# RF-Gen_Controller.net
KiCad netlist of a schematic drawn in EAGLE
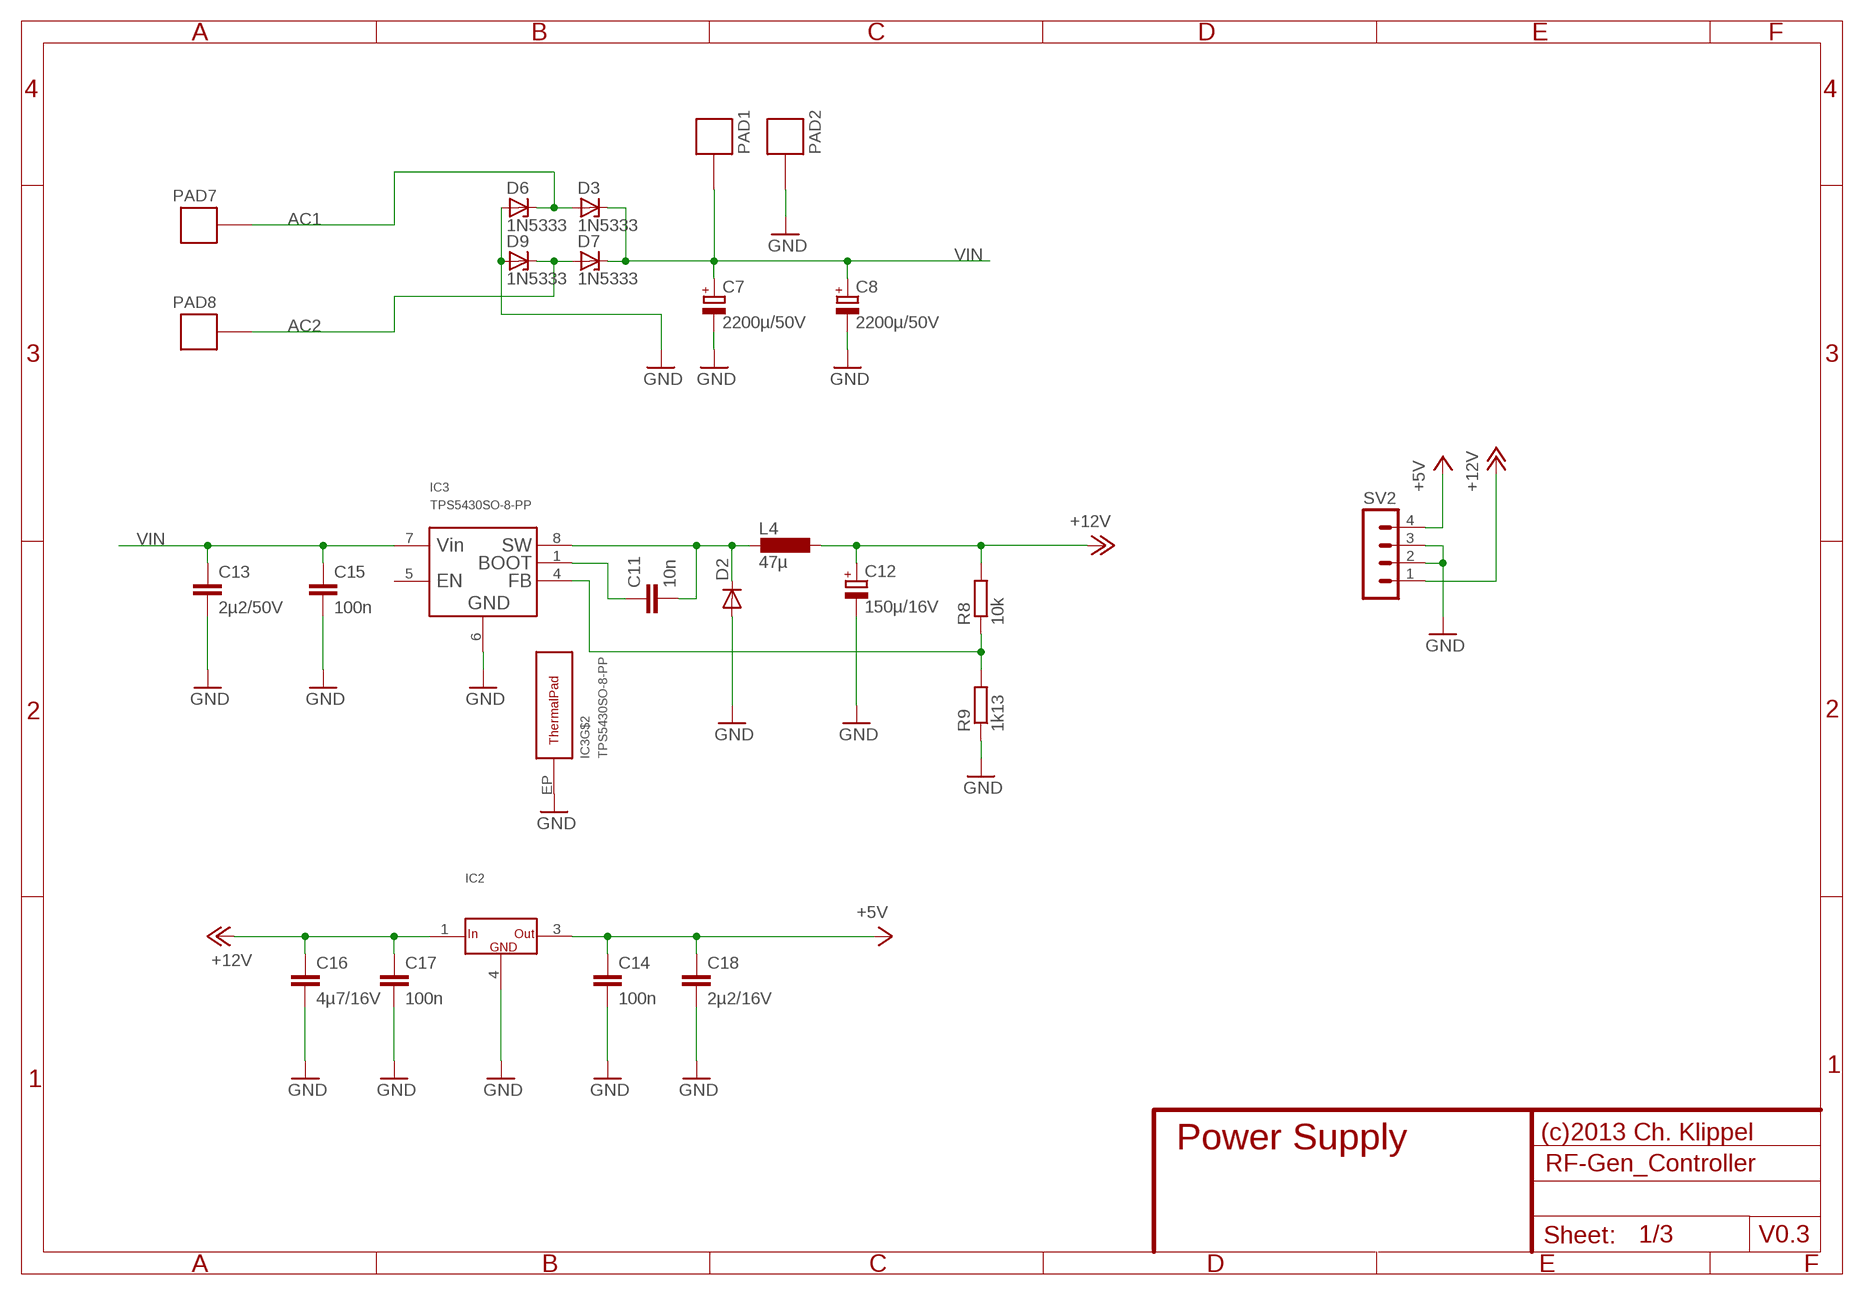
[diagram p0: schematic, sheet 1]
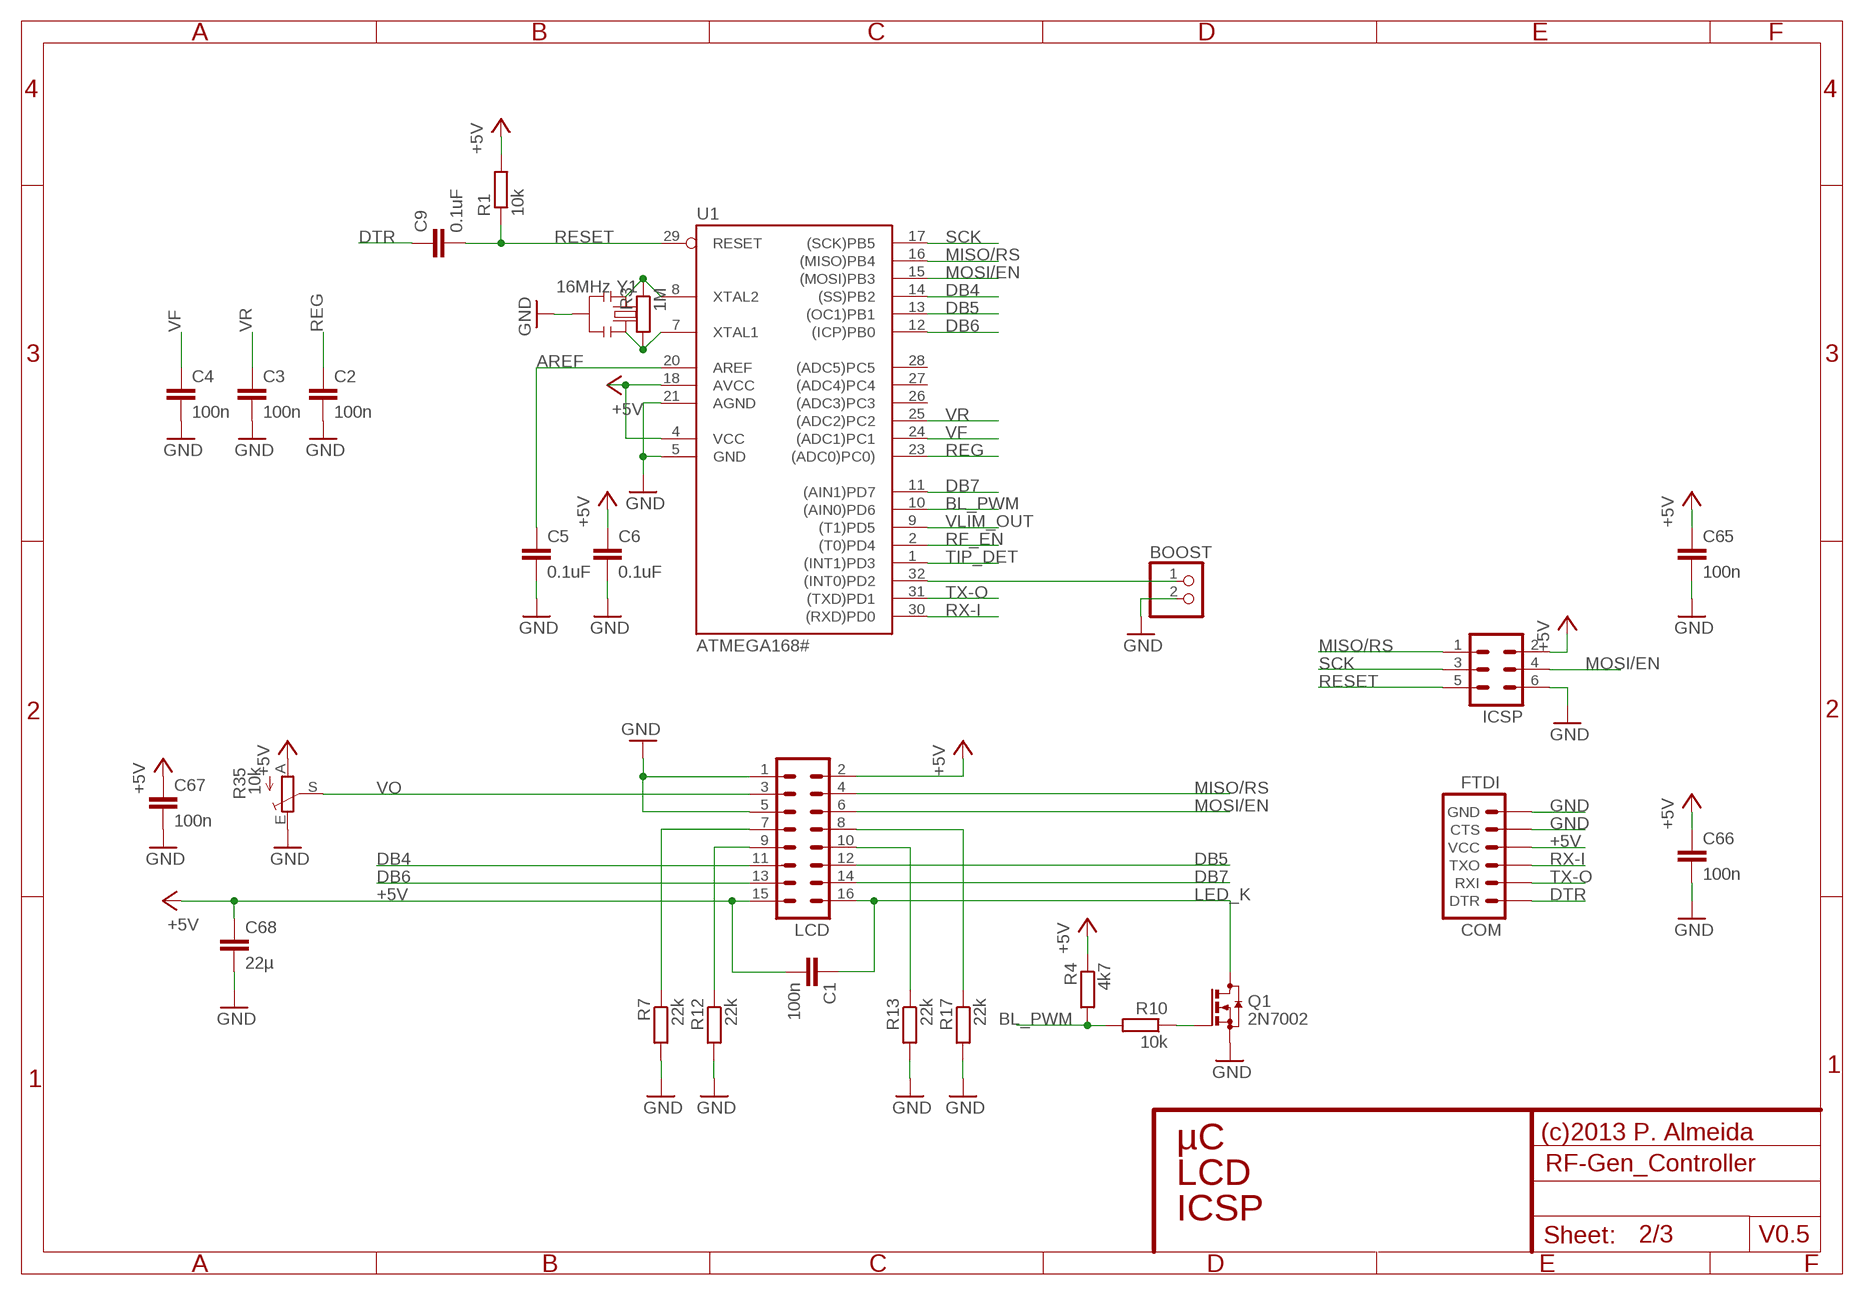
[diagram p1: schematic, sheet 2]
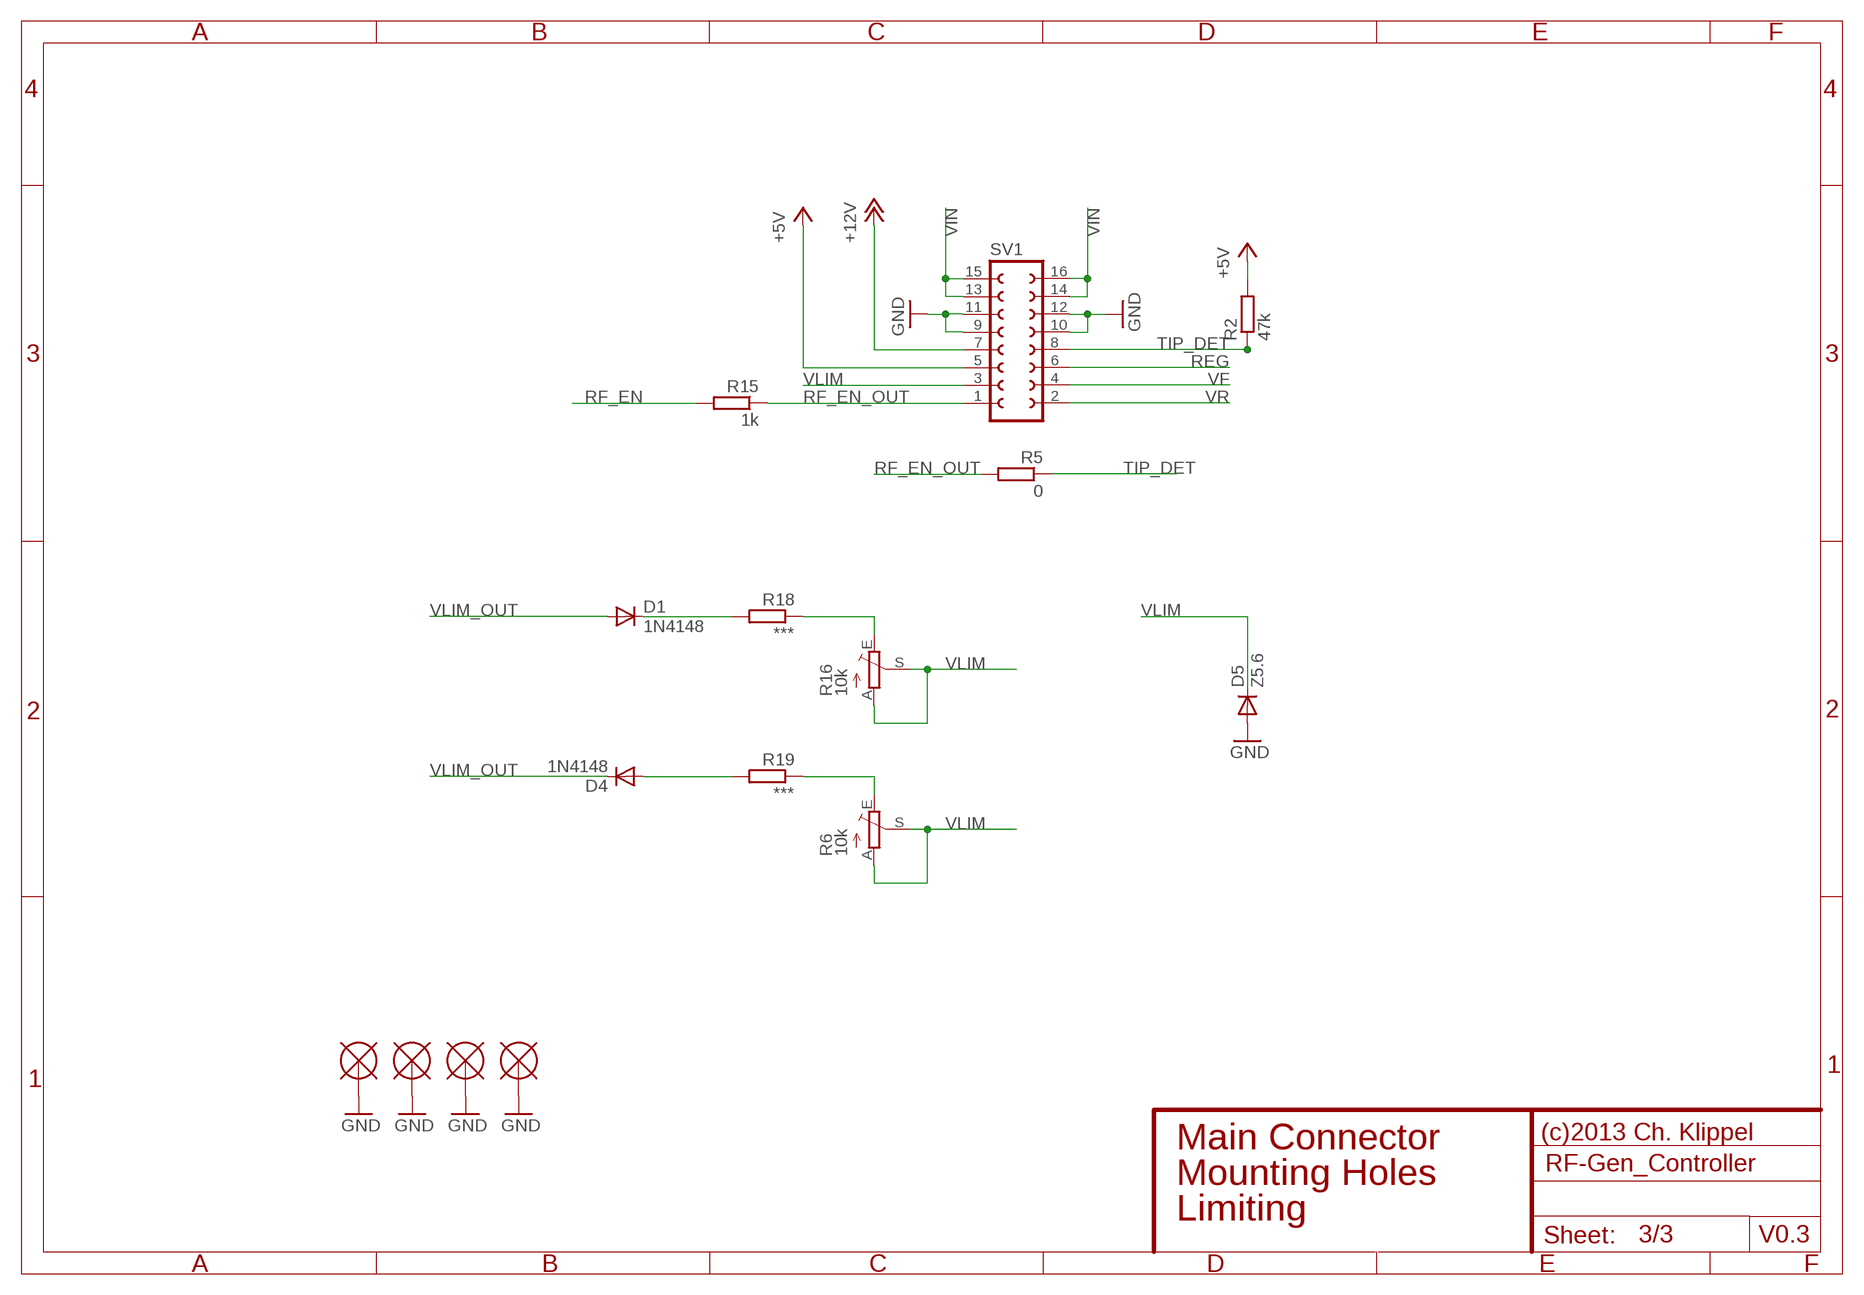
[diagram p2: schematic, sheet 3]

(export (version "E")
  (design (tool "Eeschema 10.0.6"))
  (components
    (comp (ref "D1")
      (value "1N4148")
      (footprint "eagle-import:LL-34")
      (libsource (lib "eagle-import") (part "DIODE-LL-34"))
    )
    (comp (ref "D4")
      (value "1N4148")
      (footprint "eagle-import:LL-34")
      (libsource (lib "eagle-import") (part "DIODE-LL-34"))
    )
    (comp (ref "D5")
      (value "Z5.6")
      (footprint "eagle-import:LL-34")
      (libsource (lib "eagle-import") (part "DIODE-LL-34"))
    )
    (comp (ref "R2")
      (value "47k")
      (footprint "eagle-import:R_0805_REFLOW")
      (libsource (lib "eagle-import") (part "R-EU-0805"))
    )
    (comp (ref "R5")
      (value "0")
      (footprint "eagle-import:R_0805_REFLOW")
      (libsource (lib "eagle-import") (part "R-EU-0805"))
    )
    (comp (ref "R6")
      (value "10k")
      (footprint "eagle-import:3364W")
      (libsource (lib "eagle-import") (part "TRIM_EU-3364W"))
    )
    (comp (ref "R15")
      (value "1k")
      (footprint "eagle-import:R_0805_REFLOW")
      (libsource (lib "eagle-import") (part "R-EU-0805"))
    )
    (comp (ref "R16")
      (value "10k")
      (footprint "eagle-import:3364W")
      (libsource (lib "eagle-import") (part "TRIM_EU-3364W"))
    )
    (comp (ref "R18")
      (value "***")
      (footprint "eagle-import:R_0805_REFLOW")
      (libsource (lib "eagle-import") (part "R-EU-0805"))
    )
    (comp (ref "R19")
      (value "***")
      (footprint "eagle-import:R_0805_REFLOW")
      (libsource (lib "eagle-import") (part "R-EU-0805"))
    )
    (comp (ref "SV1")
      (value "FE08-2")
      (footprint "eagle-import:FE08-2")
      (libsource (lib "eagle-import") (part "FE08-2"))
    )
    (comp (ref "U$6")
      (value "MOUNTPADM3_WASHER")
      (footprint "eagle-import:PAD_M3_WASHER")
      (libsource (lib "eagle-import") (part "MOUNTPADM3_WASHER"))
    )
    (comp (ref "U$7")
      (value "MOUNTPADM3_WASHER")
      (footprint "eagle-import:PAD_M3_WASHER")
      (libsource (lib "eagle-import") (part "MOUNTPADM3_WASHER"))
    )
    (comp (ref "U$8")
      (value "MOUNTPADM3_WASHER")
      (footprint "eagle-import:PAD_M3_WASHER")
      (libsource (lib "eagle-import") (part "MOUNTPADM3_WASHER"))
    )
    (comp (ref "U$9")
      (value "MOUNTPADM3_WASHER")
      (footprint "eagle-import:PAD_M3_WASHER")
      (libsource (lib "eagle-import") (part "MOUNTPADM3_WASHER"))
    )
    (comp (ref "C7")
      (value "2200µ/50V")
      (footprint "eagle-import:CAP_EEUHD1H_VERT2")
      (libsource (lib "eagle-import") (part "C-POL-EU-EEUHD1H_VERT2"))
    )
    (comp (ref "C8")
      (value "2200µ/50V")
      (footprint "eagle-import:CAP_EEUHD1H_VERT2")
      (libsource (lib "eagle-import") (part "C-POL-EU-EEUHD1H_VERT2"))
    )
    (comp (ref "C11")
      (value "10n")
      (footprint "eagle-import:C_1206_REFLOW")
      (libsource (lib "eagle-import") (part "C-EU-1206"))
    )
    (comp (ref "C12")
      (value "150µ/16V")
      (footprint "eagle-import:CAP_AL_100_108")
      (libsource (lib "eagle-import") (part "C-POL-EU-AL_100_108"))
    )
    (comp (ref "C13")
      (value "2µ2/50V")
      (footprint "eagle-import:C_1210_REFLOW")
      (libsource (lib "eagle-import") (part "C-EU-1210"))
    )
    (comp (ref "C14")
      (value "100n")
      (footprint "eagle-import:C_0805_REFLOW")
      (libsource (lib "eagle-import") (part "C-EU-0805"))
    )
    (comp (ref "C15")
      (value "100n")
      (footprint "eagle-import:C_0805_REFLOW")
      (libsource (lib "eagle-import") (part "C-EU-0805"))
    )
    (comp (ref "C16")
      (value "4µ7/16V")
      (footprint "eagle-import:C_1210_REFLOW")
      (libsource (lib "eagle-import") (part "C-EU-1210"))
    )
    (comp (ref "C17")
      (value "100n")
      (footprint "eagle-import:C_0805_REFLOW")
      (libsource (lib "eagle-import") (part "C-EU-0805"))
    )
    (comp (ref "C18")
      (value "2µ2/16V")
      (footprint "eagle-import:C_1210_REFLOW")
      (libsource (lib "eagle-import") (part "C-EU-1210"))
    )
    (comp (ref "D2")
      (value "DIODE-SMB")
      (footprint "eagle-import:SMB")
      (libsource (lib "eagle-import") (part "DIODE-SMB"))
    )
    (comp (ref "D3")
      (value "1N5333")
      (footprint "eagle-import:C1702-15")
      (libsource (lib "eagle-import") (part "1N5333"))
    )
    (comp (ref "D6")
      (value "1N5333")
      (footprint "eagle-import:C1702-15")
      (libsource (lib "eagle-import") (part "1N5333"))
    )
    (comp (ref "D7")
      (value "1N5333")
      (footprint "eagle-import:C1702-15")
      (libsource (lib "eagle-import") (part "1N5333"))
    )
    (comp (ref "D9")
      (value "1N5333")
      (footprint "eagle-import:C1702-15")
      (libsource (lib "eagle-import") (part "1N5333"))
    )
    (comp (ref "IC2")
      (value "VREG_3DPAK-3")
      (footprint "eagle-import:DPAK-3")
      (libsource (lib "eagle-import") (part "VREG_3DPAK-3"))
    )
    (comp (ref "IC3")
      (value "TPS5430SO-8-PP")
      (footprint "eagle-import:SO-8-PP")
      (libsource (lib "eagle-import") (part "TPS5430SO-8-PP"))
    )
    (comp (ref "L4")
      (value "47µ")
      (footprint "eagle-import:SSR1260")
      (libsource (lib "eagle-import") (part "L-EU-SSR1260"))
    )
    (comp (ref "PAD1")
      (value "SOLPAD5MM")
      (footprint "eagle-import:SOLPAD_5")
      (libsource (lib "eagle-import") (part "SOLPAD5MM"))
    )
    (comp (ref "PAD2")
      (value "SOLPAD5MM")
      (footprint "eagle-import:SOLPAD_5")
      (libsource (lib "eagle-import") (part "SOLPAD5MM"))
    )
    (comp (ref "PAD7")
      (value "SOLPAD5MM")
      (footprint "eagle-import:SOLPAD_5")
      (libsource (lib "eagle-import") (part "SOLPAD5MM"))
    )
    (comp (ref "PAD8")
      (value "SOLPAD5MM")
      (footprint "eagle-import:SOLPAD_5")
      (libsource (lib "eagle-import") (part "SOLPAD5MM"))
    )
    (comp (ref "R8")
      (value "10k")
      (footprint "eagle-import:R_0805_REFLOW")
      (libsource (lib "eagle-import") (part "R-EU-0805"))
    )
    (comp (ref "R9")
      (value "1k13")
      (footprint "eagle-import:R_0805_REFLOW")
      (libsource (lib "eagle-import") (part "R-EU-0805"))
    )
    (comp (ref "SV2")
      (value "MA04-1")
      (footprint "eagle-import:MA04-1")
      (libsource (lib "eagle-import") (part "MA04-1"))
    )
    (comp (ref "BOOST")
      (value "PINHD-1X2/90")
      (footprint "eagle-import:1X02_90")
      (libsource (lib "eagle-import") (part "PINHD-1X2/90"))
    )
    (comp (ref "C1")
      (value "100n")
      (footprint "eagle-import:C_0805_REFLOW")
      (libsource (lib "eagle-import") (part "C-EU-0805"))
    )
    (comp (ref "C2")
      (value "100n")
      (footprint "eagle-import:C_0805_REFLOW")
      (libsource (lib "eagle-import") (part "C-EU-0805"))
    )
    (comp (ref "C3")
      (value "100n")
      (footprint "eagle-import:C_0805_REFLOW")
      (libsource (lib "eagle-import") (part "C-EU-0805"))
    )
    (comp (ref "C4")
      (value "100n")
      (footprint "eagle-import:C_0805_REFLOW")
      (libsource (lib "eagle-import") (part "C-EU-0805"))
    )
    (comp (ref "C5")
      (value "0.1uF")
      (footprint "eagle-import:C_0805_REFLOW")
      (libsource (lib "eagle-import") (part "C-EU-0805"))
    )
    (comp (ref "C6")
      (value "0.1uF")
      (footprint "eagle-import:C_0805_REFLOW")
      (libsource (lib "eagle-import") (part "C-EU-0805"))
    )
    (comp (ref "C9")
      (value "0.1uF")
      (footprint "eagle-import:C_0805_REFLOW")
      (libsource (lib "eagle-import") (part "C-EU-0805"))
    )
    (comp (ref "C65")
      (value "100n")
      (footprint "eagle-import:C_0805_REFLOW")
      (libsource (lib "eagle-import") (part "C-EU-0805"))
    )
    (comp (ref "C66")
      (value "100n")
      (footprint "eagle-import:C_0805_REFLOW")
      (libsource (lib "eagle-import") (part "C-EU-0805"))
    )
    (comp (ref "C67")
      (value "100n")
      (footprint "eagle-import:C_0805_REFLOW")
      (libsource (lib "eagle-import") (part "C-EU-0805"))
    )
    (comp (ref "C68")
      (value "22µ")
      (footprint "eagle-import:C_1206_REFLOW")
      (libsource (lib "eagle-import") (part "C-EU-1206"))
    )
    (comp (ref "FTDI")
      (value "COM")
      (footprint "eagle-import:1X06")
      (libsource (lib "eagle-import") (part "ARDUINO_SERIAL_PROGRAMPTH"))
    )
    (comp (ref "ICSP")
      (value "ML6")
      (footprint "eagle-import:ML6")
      (libsource (lib "eagle-import") (part "ML6"))
    )
    (comp (ref "LCD")
      (value "ML16")
      (footprint "eagle-import:ML16")
      (libsource (lib "eagle-import") (part "ML16"))
    )
    (comp (ref "Q1")
      (value "2N7002")
      (footprint "eagle-import:SOT23")
      (libsource (lib "eagle-import") (part "BSS123"))
    )
    (comp (ref "R1")
      (value "10k")
      (footprint "eagle-import:R_0805_REFLOW")
      (libsource (lib "eagle-import") (part "R-EU-0805"))
    )
    (comp (ref "R3")
      (value "1M")
      (footprint "eagle-import:R_0805_REFLOW")
      (libsource (lib "eagle-import") (part "R-EU-0805"))
    )
    (comp (ref "R4")
      (value "4k7")
      (footprint "eagle-import:R_0805_REFLOW")
      (libsource (lib "eagle-import") (part "R-EU-0805"))
    )
    (comp (ref "R7")
      (value "22k")
      (footprint "eagle-import:R_0805_REFLOW")
      (libsource (lib "eagle-import") (part "R-EU-0805"))
    )
    (comp (ref "R10")
      (value "10k")
      (footprint "eagle-import:R_0805_REFLOW")
      (libsource (lib "eagle-import") (part "R-EU-0805"))
    )
    (comp (ref "R12")
      (value "22k")
      (footprint "eagle-import:R_0805_REFLOW")
      (libsource (lib "eagle-import") (part "R-EU-0805"))
    )
    (comp (ref "R13")
      (value "22k")
      (footprint "eagle-import:R_0805_REFLOW")
      (libsource (lib "eagle-import") (part "R-EU-0805"))
    )
    (comp (ref "R17")
      (value "22k")
      (footprint "eagle-import:R_0805_REFLOW")
      (libsource (lib "eagle-import") (part "R-EU-0805"))
    )
    (comp (ref "R35")
      (value "10k")
      (footprint "eagle-import:3364W")
      (libsource (lib "eagle-import") (part "TRIM_EU-3364W"))
    )
    (comp (ref "U1")
      (value "ATMEGA168#")
      (footprint "eagle-import:TQFP32-08")
      (libsource (lib "eagle-import") (part "AT90S4433A"))
    )
    (comp (ref "Y1")
      (value "16MHz")
      (footprint "eagle-import:RESONATOR-SMD")
      (libsource (lib "eagle-import") (part "RESONATORSMD"))
    )
  )
  (nets
    (net (code "1") (name "+5V") (class "Default")
      (node (ref "C1") (pin "P$2") (pinfunction "2_P$2") (pintype "passive"))
      (node (ref "C14") (pin "P$1") (pinfunction "1_P$1") (pintype "passive"))
      (node (ref "C18") (pin "P$1") (pinfunction "1_P$1") (pintype "passive"))
      (node (ref "C6") (pin "P$1") (pinfunction "1_P$1") (pintype "passive"))
      (node (ref "C65") (pin "P$1") (pinfunction "1_P$1") (pintype "passive"))
      (node (ref "C66") (pin "P$1") (pinfunction "1_P$1") (pintype "passive"))
      (node (ref "C67") (pin "P$1") (pinfunction "1_P$1") (pintype "passive"))
      (node (ref "C68") (pin "P$1") (pinfunction "1_P$1") (pintype "passive"))
      (node (ref "FTDI") (pin "4") (pinfunction "VCC_4") (pintype "passive"))
      (node (ref "IC2") (pin "3") (pinfunction "OUT_3") (pintype "bidirectional"))
      (node (ref "ICSP") (pin "2") (pinfunction "2_2") (pintype "passive"))
      (node (ref "LCD") (pin "15") (pinfunction "15_15") (pintype "passive"))
      (node (ref "LCD") (pin "2") (pinfunction "2_2") (pintype "passive"))
      (node (ref "R1") (pin "P$2") (pinfunction "2_P$2") (pintype "passive"))
      (node (ref "R2") (pin "P$2") (pinfunction "2_P$2") (pintype "passive"))
      (node (ref "R35") (pin "A") (pinfunction "A_A") (pintype "passive"))
      (node (ref "R4") (pin "P$1") (pinfunction "1_P$1") (pintype "passive"))
      (node (ref "SV1") (pin "5") (pinfunction "5_5") (pintype "passive"))
      (node (ref "SV2") (pin "4") (pinfunction "4_4") (pintype "passive"))
      (node (ref "U1") (pin "18") (pinfunction "AVCC_18") (pintype "power_in"))
      (node (ref "U1") (pin "4") (pinfunction "VCC_4") (pintype "power_in"))
    )
    (net (code "2") (name "+12V") (class "Default")
      (node (ref "C12") (pin "+") (pinfunction "+_+") (pintype "passive"))
      (node (ref "C16") (pin "P$1") (pinfunction "1_P$1") (pintype "passive"))
      (node (ref "C17") (pin "P$1") (pinfunction "1_P$1") (pintype "passive"))
      (node (ref "IC2") (pin "1") (pinfunction "IN_1") (pintype "bidirectional"))
      (node (ref "L4") (pin "1") (pinfunction "1_1") (pintype "passive"))
      (node (ref "R8") (pin "P$2") (pinfunction "2_P$2") (pintype "passive"))
      (node (ref "SV1") (pin "7") (pinfunction "7_7") (pintype "passive"))
      (node (ref "SV2") (pin "1") (pinfunction "1_1") (pintype "passive"))
    )
    (net (code "3") (name "AC1") (class "Default")
      (node (ref "D3") (pin "A") (pinfunction "A_A") (pintype "passive"))
      (node (ref "D6") (pin "C") (pinfunction "C_C") (pintype "passive"))
      (node (ref "PAD7") (pin "P$1") (pinfunction "P$1_P$1") (pintype "bidirectional"))
    )
    (net (code "4") (name "AC2") (class "Default")
      (node (ref "D7") (pin "A") (pinfunction "A_A") (pintype "passive"))
      (node (ref "D9") (pin "C") (pinfunction "C_C") (pintype "passive"))
      (node (ref "PAD8") (pin "P$1") (pinfunction "P$1_P$1") (pintype "bidirectional"))
    )
    (net (code "5") (name "AREF") (class "Default")
      (node (ref "C5") (pin "P$1") (pinfunction "1_P$1") (pintype "passive"))
      (node (ref "U1") (pin "20") (pinfunction "AREF_20") (pintype "power_in"))
    )
    (net (code "6") (name "BL_PWM") (class "Default")
      (node (ref "R10") (pin "P$2") (pinfunction "2_P$2") (pintype "passive"))
      (node (ref "R4") (pin "P$2") (pinfunction "2_P$2") (pintype "passive"))
      (node (ref "U1") (pin "10") (pinfunction "(AIN0)PD6_10") (pintype "bidirectional"))
    )
    (net (code "7") (name "DB4") (class "Default")
      (node (ref "LCD") (pin "11") (pinfunction "11_11") (pintype "passive"))
      (node (ref "U1") (pin "14") (pinfunction "(SS)PB2_14") (pintype "bidirectional"))
    )
    (net (code "8") (name "DB5") (class "Default")
      (node (ref "LCD") (pin "12") (pinfunction "12_12") (pintype "passive"))
      (node (ref "U1") (pin "13") (pinfunction "(OC1)PB1_13") (pintype "bidirectional"))
    )
    (net (code "9") (name "DB6") (class "Default")
      (node (ref "LCD") (pin "13") (pinfunction "13_13") (pintype "passive"))
      (node (ref "U1") (pin "12") (pinfunction "(ICP)PB0_12") (pintype "bidirectional"))
    )
    (net (code "10") (name "DB7") (class "Default")
      (node (ref "LCD") (pin "14") (pinfunction "14_14") (pintype "passive"))
      (node (ref "U1") (pin "11") (pinfunction "(AIN1)PD7_11") (pintype "bidirectional"))
    )
    (net (code "11") (name "DTR") (class "Default")
      (node (ref "C9") (pin "P$1") (pinfunction "1_P$1") (pintype "passive"))
      (node (ref "FTDI") (pin "1") (pinfunction "DTR_1") (pintype "passive"))
    )
    (net (code "12") (name "GND") (class "Default")
      (node (ref "BOOST") (pin "2") (pinfunction "2_2") (pintype "passive"))
      (node (ref "C12") (pin "-") (pinfunction "-_-") (pintype "passive"))
      (node (ref "C13") (pin "P$2") (pinfunction "2_P$2") (pintype "passive"))
      (node (ref "C14") (pin "P$2") (pinfunction "2_P$2") (pintype "passive"))
      (node (ref "C15") (pin "P$2") (pinfunction "2_P$2") (pintype "passive"))
      (node (ref "C16") (pin "P$2") (pinfunction "2_P$2") (pintype "passive"))
      (node (ref "C17") (pin "P$2") (pinfunction "2_P$2") (pintype "passive"))
      (node (ref "C18") (pin "P$2") (pinfunction "2_P$2") (pintype "passive"))
      (node (ref "C2") (pin "P$2") (pinfunction "2_P$2") (pintype "passive"))
      (node (ref "C3") (pin "P$2") (pinfunction "2_P$2") (pintype "passive"))
      (node (ref "C4") (pin "P$2") (pinfunction "2_P$2") (pintype "passive"))
      (node (ref "C5") (pin "P$2") (pinfunction "2_P$2") (pintype "passive"))
      (node (ref "C6") (pin "P$2") (pinfunction "2_P$2") (pintype "passive"))
      (node (ref "C65") (pin "P$2") (pinfunction "2_P$2") (pintype "passive"))
      (node (ref "C66") (pin "P$2") (pinfunction "2_P$2") (pintype "passive"))
      (node (ref "C67") (pin "P$2") (pinfunction "2_P$2") (pintype "passive"))
      (node (ref "C68") (pin "P$2") (pinfunction "2_P$2") (pintype "passive"))
      (node (ref "C7") (pin "-") (pinfunction "-_-") (pintype "passive"))
      (node (ref "C8") (pin "-") (pinfunction "-_-") (pintype "passive"))
      (node (ref "D2") (pin "A") (pinfunction "A_A") (pintype "passive"))
      (node (ref "D5") (pin "A") (pinfunction "A_A") (pintype "passive"))
      (node (ref "D6") (pin "A") (pinfunction "A_A") (pintype "passive"))
      (node (ref "D9") (pin "A") (pinfunction "A_A") (pintype "passive"))
      (node (ref "FTDI") (pin "5") (pinfunction "CTS_5") (pintype "passive"))
      (node (ref "FTDI") (pin "6") (pinfunction "GND_6") (pintype "passive"))
      (node (ref "IC2") (pin "4") (pinfunction "GND_4") (pintype "bidirectional"))
      (node (ref "IC3") (pin "6") (pinfunction "GND_6") (pintype "bidirectional"))
      (node (ref "IC3") (pin "EP") (pinfunction "THERMALPAD_EP") (pintype "bidirectional"))
      (node (ref "ICSP") (pin "6") (pinfunction "6_6") (pintype "passive"))
      (node (ref "LCD") (pin "1") (pinfunction "1_1") (pintype "passive"))
      (node (ref "LCD") (pin "5") (pinfunction "5_5") (pintype "passive"))
      (node (ref "PAD2") (pin "P$1") (pinfunction "P$1_P$1") (pintype "bidirectional"))
      (node (ref "Q1") (pin "2") (pinfunction "S_2") (pintype "passive"))
      (node (ref "R12") (pin "P$2") (pinfunction "2_P$2") (pintype "passive"))
      (node (ref "R13") (pin "P$2") (pinfunction "2_P$2") (pintype "passive"))
      (node (ref "R17") (pin "P$2") (pinfunction "2_P$2") (pintype "passive"))
      (node (ref "R35") (pin "E") (pinfunction "E_E") (pintype "passive"))
      (node (ref "R7") (pin "P$2") (pinfunction "2_P$2") (pintype "passive"))
      (node (ref "R9") (pin "P$1") (pinfunction "1_P$1") (pintype "passive"))
      (node (ref "SV1") (pin "10") (pinfunction "10_10") (pintype "passive"))
      (node (ref "SV1") (pin "11") (pinfunction "11_11") (pintype "passive"))
      (node (ref "SV1") (pin "12") (pinfunction "12_12") (pintype "passive"))
      (node (ref "SV1") (pin "9") (pinfunction "9_9") (pintype "passive"))
      (node (ref "SV2") (pin "2") (pinfunction "2_2") (pintype "passive"))
      (node (ref "SV2") (pin "3") (pinfunction "3_3") (pintype "passive"))
      (node (ref "U$6") (pin "P$1") (pinfunction "P$1_P$1") (pintype "bidirectional"))
      (node (ref "U$7") (pin "P$1") (pinfunction "P$1_P$1") (pintype "bidirectional"))
      (node (ref "U$8") (pin "P$1") (pinfunction "P$1_P$1") (pintype "bidirectional"))
      (node (ref "U$9") (pin "P$1") (pinfunction "P$1_P$1") (pintype "bidirectional"))
      (node (ref "U1") (pin "21") (pinfunction "AGND_21") (pintype "power_in"))
      (node (ref "U1") (pin "5") (pinfunction "GND_5") (pintype "power_in"))
      (node (ref "Y1") (pin "2") (pinfunction "2_2") (pintype "passive"))
    )
    (net (code "13") (name "LED_K") (class "Default")
      (node (ref "C1") (pin "P$1") (pinfunction "1_P$1") (pintype "passive"))
      (node (ref "LCD") (pin "16") (pinfunction "16_16") (pintype "passive"))
      (node (ref "Q1") (pin "3") (pinfunction "D_3") (pintype "passive"))
    )
    (net (code "14") (name "MISO{slash}RS") (class "Default")
      (node (ref "ICSP") (pin "1") (pinfunction "1_1") (pintype "passive"))
      (node (ref "LCD") (pin "4") (pinfunction "4_4") (pintype "passive"))
      (node (ref "U1") (pin "16") (pinfunction "(MISO)PB4_16") (pintype "bidirectional"))
    )
    (net (code "15") (name "MOSI{slash}EN") (class "Default")
      (node (ref "ICSP") (pin "4") (pinfunction "4_4") (pintype "passive"))
      (node (ref "LCD") (pin "6") (pinfunction "6_6") (pintype "passive"))
      (node (ref "U1") (pin "15") (pinfunction "(MOSI)PB3_15") (pintype "bidirectional"))
    )
    (net (code "16") (name "Net-(C11-1)") (class "Default")
      (node (ref "C11") (pin "P$1") (pinfunction "1_P$1") (pintype "passive"))
      (node (ref "IC3") (pin "1") (pinfunction "BOOT_1") (pintype "bidirectional"))
    )
    (net (code "17") (name "Net-(C11-2)") (class "Default")
      (node (ref "C11") (pin "P$2") (pinfunction "2_P$2") (pintype "passive"))
      (node (ref "D2") (pin "C") (pinfunction "C_C") (pintype "passive"))
      (node (ref "IC3") (pin "8") (pinfunction "SW_8") (pintype "bidirectional"))
      (node (ref "L4") (pin "2") (pinfunction "2_2") (pintype "passive"))
    )
    (net (code "18") (name "Net-(IC3A-FB)") (class "Default")
      (node (ref "IC3") (pin "4") (pinfunction "FB_4") (pintype "bidirectional"))
      (node (ref "R8") (pin "P$1") (pinfunction "1_P$1") (pintype "passive"))
      (node (ref "R9") (pin "P$2") (pinfunction "2_P$2") (pintype "passive"))
    )
    (net (code "19") (name "Net-(Q1-G)") (class "Default")
      (node (ref "Q1") (pin "1") (pinfunction "G_1") (pintype "passive"))
      (node (ref "R10") (pin "P$1") (pinfunction "1_P$1") (pintype "passive"))
    )
    (net (code "20") (name "Net-(R3-1)") (class "Default")
      (node (ref "R3") (pin "P$1") (pinfunction "1_P$1") (pintype "passive"))
      (node (ref "U1") (pin "8") (pinfunction "XTAL2_8") (pintype "bidirectional"))
      (node (ref "Y1") (pin "1") (pinfunction "1_1") (pintype "passive"))
    )
    (net (code "21") (name "Net-(R3-2)") (class "Default")
      (node (ref "R3") (pin "P$2") (pinfunction "2_P$2") (pintype "passive"))
      (node (ref "U1") (pin "7") (pinfunction "XTAL1_7") (pintype "bidirectional"))
      (node (ref "Y1") (pin "3") (pinfunction "3_3") (pintype "passive"))
    )
    (net (code "22") (name "Net-(R7-1)") (class "Default")
      (node (ref "LCD") (pin "7") (pinfunction "7_7") (pintype "passive"))
      (node (ref "R7") (pin "P$1") (pinfunction "1_P$1") (pintype "passive"))
    )
    (net (code "23") (name "Net-(R12-1)") (class "Default")
      (node (ref "LCD") (pin "9") (pinfunction "9_9") (pintype "passive"))
      (node (ref "R12") (pin "P$1") (pinfunction "1_P$1") (pintype "passive"))
    )
    (net (code "24") (name "Net-(R13-1)") (class "Default")
      (node (ref "LCD") (pin "10") (pinfunction "10_10") (pintype "passive"))
      (node (ref "R13") (pin "P$1") (pinfunction "1_P$1") (pintype "passive"))
    )
    (net (code "25") (name "Net-(R17-1)") (class "Default")
      (node (ref "LCD") (pin "8") (pinfunction "8_8") (pintype "passive"))
      (node (ref "R17") (pin "P$1") (pinfunction "1_P$1") (pintype "passive"))
    )
    (net (code "26") (name "Net-(R18-1)") (class "Default")
      (node (ref "R16") (pin "E") (pinfunction "E_E") (pintype "passive"))
      (node (ref "R18") (pin "P$1") (pinfunction "1_P$1") (pintype "passive"))
    )
    (net (code "27") (name "Net-(R18-2)") (class "Default")
      (node (ref "D1") (pin "C") (pinfunction "C_C") (pintype "passive"))
      (node (ref "R18") (pin "P$2") (pinfunction "2_P$2") (pintype "passive"))
    )
    (net (code "28") (name "Net-(R19-1)") (class "Default")
      (node (ref "R19") (pin "P$1") (pinfunction "1_P$1") (pintype "passive"))
      (node (ref "R6") (pin "E") (pinfunction "E_E") (pintype "passive"))
    )
    (net (code "29") (name "Net-(R19-2)") (class "Default")
      (node (ref "D4") (pin "A") (pinfunction "A_A") (pintype "passive"))
      (node (ref "R19") (pin "P$2") (pinfunction "2_P$2") (pintype "passive"))
    )
    (net (code "30") (name "Net-(U1-(INT0)PD2)") (class "Default")
      (node (ref "BOOST") (pin "1") (pinfunction "1_1") (pintype "passive"))
      (node (ref "U1") (pin "32") (pinfunction "(INT0)PD2_32") (pintype "bidirectional"))
    )
    (net (code "31") (name "REG") (class "Default")
      (node (ref "C2") (pin "P$1") (pinfunction "1_P$1") (pintype "passive"))
      (node (ref "SV1") (pin "6") (pinfunction "6_6") (pintype "passive"))
      (node (ref "U1") (pin "23") (pinfunction "(ADC0)PC0)_23") (pintype "bidirectional"))
    )
    (net (code "32") (name "RESET") (class "Default")
      (node (ref "C9") (pin "P$2") (pinfunction "2_P$2") (pintype "passive"))
      (node (ref "ICSP") (pin "5") (pinfunction "5_5") (pintype "passive"))
      (node (ref "R1") (pin "P$1") (pinfunction "1_P$1") (pintype "passive"))
      (node (ref "U1") (pin "29") (pinfunction "RESET_29") (pintype "input"))
    )
    (net (code "33") (name "RF_EN") (class "Default")
      (node (ref "R15") (pin "P$2") (pinfunction "2_P$2") (pintype "passive"))
      (node (ref "U1") (pin "2") (pinfunction "(T0)PD4_2") (pintype "bidirectional"))
    )
    (net (code "34") (name "RF_EN_OUT") (class "Default")
      (node (ref "R15") (pin "P$1") (pinfunction "1_P$1") (pintype "passive"))
      (node (ref "R5") (pin "P$2") (pinfunction "2_P$2") (pintype "passive"))
      (node (ref "SV1") (pin "1") (pinfunction "1_1") (pintype "passive"))
    )
    (net (code "35") (name "RX-I") (class "Default")
      (node (ref "FTDI") (pin "3") (pinfunction "TXO_3") (pintype "passive"))
      (node (ref "U1") (pin "30") (pinfunction "(RXD)PD0_30") (pintype "bidirectional"))
    )
    (net (code "36") (name "SCK") (class "Default")
      (node (ref "ICSP") (pin "3") (pinfunction "3_3") (pintype "passive"))
      (node (ref "U1") (pin "17") (pinfunction "(SCK)PB5_17") (pintype "bidirectional"))
    )
    (net (code "37") (name "TIP_DET") (class "Default")
      (node (ref "R2") (pin "P$1") (pinfunction "1_P$1") (pintype "passive"))
      (node (ref "R5") (pin "P$1") (pinfunction "1_P$1") (pintype "passive"))
      (node (ref "SV1") (pin "8") (pinfunction "8_8") (pintype "passive"))
      (node (ref "U1") (pin "1") (pinfunction "(INT1)PD3_1") (pintype "bidirectional"))
    )
    (net (code "38") (name "TX-O") (class "Default")
      (node (ref "FTDI") (pin "2") (pinfunction "RXI_2") (pintype "passive"))
      (node (ref "U1") (pin "31") (pinfunction "(TXD)PD1_31") (pintype "bidirectional"))
    )
    (net (code "39") (name "VF") (class "Default")
      (node (ref "C4") (pin "P$1") (pinfunction "1_P$1") (pintype "passive"))
      (node (ref "SV1") (pin "4") (pinfunction "4_4") (pintype "passive"))
      (node (ref "U1") (pin "24") (pinfunction "(ADC1)PC1_24") (pintype "bidirectional"))
    )
    (net (code "40") (name "VIN") (class "Default")
      (node (ref "C13") (pin "P$1") (pinfunction "1_P$1") (pintype "passive"))
      (node (ref "C15") (pin "P$1") (pinfunction "1_P$1") (pintype "passive"))
      (node (ref "C7") (pin "+") (pinfunction "+_+") (pintype "passive"))
      (node (ref "C8") (pin "+") (pinfunction "+_+") (pintype "passive"))
      (node (ref "D3") (pin "C") (pinfunction "C_C") (pintype "passive"))
      (node (ref "D7") (pin "C") (pinfunction "C_C") (pintype "passive"))
      (node (ref "IC3") (pin "7") (pinfunction "VIN_7") (pintype "bidirectional"))
      (node (ref "PAD1") (pin "P$1") (pinfunction "P$1_P$1") (pintype "bidirectional"))
      (node (ref "SV1") (pin "13") (pinfunction "13_13") (pintype "passive"))
      (node (ref "SV1") (pin "14") (pinfunction "14_14") (pintype "passive"))
      (node (ref "SV1") (pin "15") (pinfunction "15_15") (pintype "passive"))
      (node (ref "SV1") (pin "16") (pinfunction "16_16") (pintype "passive"))
    )
    (net (code "41") (name "VLIM") (class "Default")
      (node (ref "D5") (pin "C") (pinfunction "C_C") (pintype "passive"))
      (node (ref "R16") (pin "A") (pinfunction "A_A") (pintype "passive"))
      (node (ref "R16") (pin "S") (pinfunction "S_S") (pintype "passive"))
      (node (ref "R6") (pin "A") (pinfunction "A_A") (pintype "passive"))
      (node (ref "R6") (pin "S") (pinfunction "S_S") (pintype "passive"))
      (node (ref "SV1") (pin "3") (pinfunction "3_3") (pintype "passive"))
    )
    (net (code "42") (name "VLIM_OUT") (class "Default")
      (node (ref "D1") (pin "A") (pinfunction "A_A") (pintype "passive"))
      (node (ref "D4") (pin "C") (pinfunction "C_C") (pintype "passive"))
      (node (ref "U1") (pin "9") (pinfunction "(T1)PD5_9") (pintype "bidirectional"))
    )
    (net (code "43") (name "VO") (class "Default")
      (node (ref "LCD") (pin "3") (pinfunction "3_3") (pintype "passive"))
      (node (ref "R35") (pin "S") (pinfunction "S_S") (pintype "passive"))
    )
    (net (code "44") (name "VR") (class "Default")
      (node (ref "C3") (pin "P$1") (pinfunction "1_P$1") (pintype "passive"))
      (node (ref "SV1") (pin "2") (pinfunction "2_2") (pintype "passive"))
      (node (ref "U1") (pin "25") (pinfunction "(ADC2)PC2_25") (pintype "bidirectional"))
    )
    (net (code "45") (name "unconnected-(IC3A-EN-Pad5)") (class "Default")
      (node (ref "IC3") (pin "5") (pinfunction "EN_5") (pintype "bidirectional"))
    )
    (net (code "46") (name "unconnected-(U1-(ADC3)PC3-Pad26)") (class "Default")
      (node (ref "U1") (pin "26") (pinfunction "(ADC3)PC3_26") (pintype "bidirectional"))
    )
    (net (code "47") (name "unconnected-(U1-(ADC4)PC4-Pad27)") (class "Default")
      (node (ref "U1") (pin "27") (pinfunction "(ADC4)PC4_27") (pintype "bidirectional"))
    )
    (net (code "48") (name "unconnected-(U1-(ADC5)PC5-Pad28)") (class "Default")
      (node (ref "U1") (pin "28") (pinfunction "(ADC5)PC5_28") (pintype "bidirectional"))
    )
  )
)
